# design.net
KiCad netlist of a schematic drawn in Altium Designer
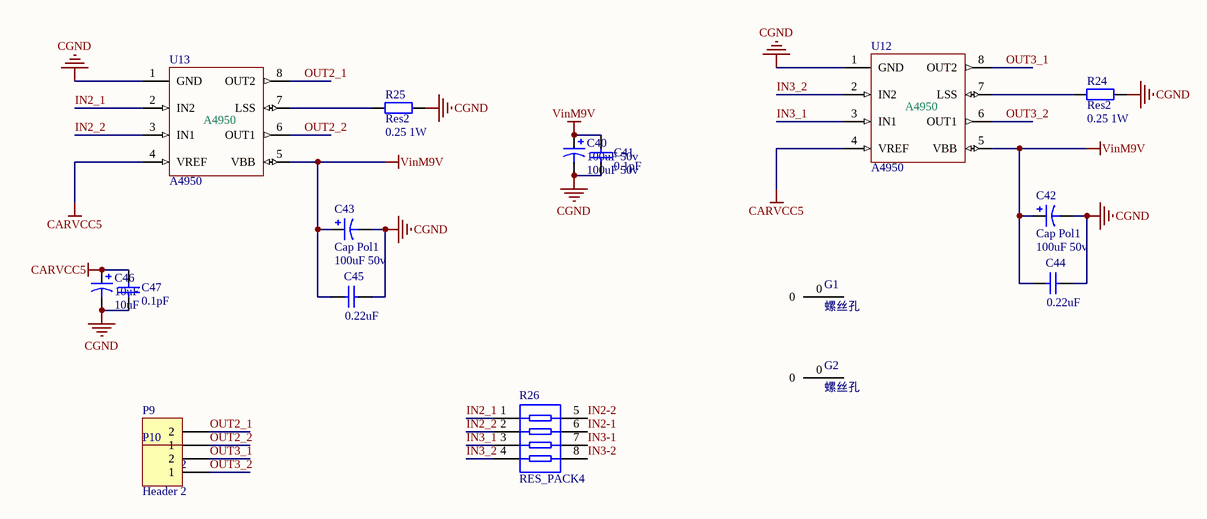
[diagram p0: 电机驱动.SchDoc]

(export (version "E")
  (design (tool "Eeschema 10.0.6"))
  (components
    (comp (ref "C40")
      (value "100uF 50v")
      (footprint "电容HONOR_63X77")
      (description "Polarized Capacitor (Radial)")
      (fields (field (name "ALTIUM_VALUE") "100uF 50v") (field (name "PUBLISHER") "Altium Limited"))
      (libsource (lib "Miscellaneous Devices") (part "Cap Pol1"))
    )
    (comp (ref "C41")
      (value "0.1pF")
      (footprint "LC-0603_C")
      (description "Capacitor")
      (fields (field (name "Comment") "Cap") (field (name "PUBLISHER") "Altium Limited"))
      (libsource (lib "Miscellaneous Devices") (part "Cap"))
    )
    (comp (ref "C42")
      (value "Cap Pol1")
      (footprint "100UF")
      (description "Polarized Capacitor (Radial)")
      (fields (field (name "ALTIUM_VALUE") "100uF 50v") (field (name "PUBLISHER") "Altium Limited"))
      (libsource (lib "Miscellaneous Devices") (part "Cap Pol1"))
    )
    (comp (ref "C43")
      (value "Cap Pol1")
      (footprint "100UF")
      (description "Polarized Capacitor (Radial)")
      (fields (field (name "ALTIUM_VALUE") "100uF 50v") (field (name "PUBLISHER") "Altium Limited"))
      (libsource (lib "Miscellaneous Devices") (part "Cap Pol1"))
    )
    (comp (ref "C44")
      (value "0.22uF")
      (footprint "LC-0603_C")
      (description "Capacitor")
      (fields (field (name "PUBLISHER") "Altium Limited"))
      (libsource (lib "Miscellaneous Devices") (part "Cap"))
    )
    (comp (ref "C45")
      (value "0.22uF")
      (footprint "LC-0603_C")
      (description "Capacitor")
      (fields (field (name "PUBLISHER") "Altium Limited"))
      (libsource (lib "Miscellaneous Devices") (part "Cap"))
    )
    (comp (ref "C46")
      (value "10uF")
      (footprint "电容HONOR_63X77")
      (description "Polarized Capacitor (Radial)")
      (fields (field (name "ALTIUM_VALUE") "10uF") (field (name "PUBLISHER") "Altium Limited"))
      (libsource (lib "Miscellaneous Devices") (part "Cap Pol1"))
    )
    (comp (ref "C47")
      (value "0.1pF")
      (footprint "LC-0603_C")
      (description "Capacitor")
      (fields (field (name "Comment") "Cap") (field (name "PUBLISHER") "Altium Limited"))
      (libsource (lib "Miscellaneous Devices") (part "Cap"))
    )
    (comp (ref "G1") (value "螺丝孔") (footprint "M3螺丝孔") (libsource (lib "ROS_CAR_LIB") (part "螺丝孔")))
    (comp (ref "G2") (value "螺丝孔") (footprint "M3螺丝孔") (libsource (lib "ROS_CAR_LIB") (part "螺丝孔")))
    (comp (ref "P9")
      (value "Header 2")
      (footprint "HDR1X2")
      (description "Header, 2-Pin")
      (fields (field (name "PUBLISHER") "Altium Limited"))
      (libsource (lib "Miscellaneous Connectors") (part "Header 2"))
    )
    (comp (ref "P10")
      (value "Header 2")
      (footprint "HDR1X2")
      (description "Header, 2-Pin")
      (fields (field (name "PUBLISHER") "Altium Limited"))
      (libsource (lib "Miscellaneous Connectors") (part "Header 2"))
    )
    (comp (ref "R24")
      (value "Res2")
      (footprint "LC-2512_R")
      (description "Resistor")
      (fields (field (name "ALTIUM_VALUE") "0.25 1W") (field (name "PUBLISHER") "Altium Limited"))
      (libsource (lib "Miscellaneous Devices") (part "Res2"))
    )
    (comp (ref "R25")
      (value "Res2")
      (footprint "LC-2512_R")
      (description "Resistor")
      (fields (field (name "ALTIUM_VALUE") "0.25 1W") (field (name "PUBLISHER") "Altium Limited"))
      (libsource (lib "Miscellaneous Devices") (part "Res2"))
    )
    (comp (ref "R26") (value "RES_PACK4") (footprint "RES4") (libsource (lib "ARAMYLIB") (part "RES_PACK4")))
    (comp (ref "U12")
      (value "A4950")
      (footprint "LC-SOIC-8_150mil")
      (libsource (lib "ROS_CAR_LIB") (part "A4950"))
    )
    (comp (ref "U13")
      (value "A4950")
      (footprint "LC-SOIC-8_150mil")
      (libsource (lib "ROS_CAR_LIB") (part "A4950"))
    )
  )
  (nets
    (net (code "1") (name "/IN2-1") (class "Default")
      (node (ref "R26") (pin "6") (pinfunction "6_6") (pintype "passive"))
    )
    (net (code "2") (name "/IN2-2") (class "Default")
      (node (ref "R26") (pin "5") (pinfunction "5_5") (pintype "passive"))
    )
    (net (code "3") (name "/IN2_1") (class "Default")
      (node (ref "R26") (pin "1") (pinfunction "1_1") (pintype "passive"))
      (node (ref "U13") (pin "2") (pinfunction "IN2_2") (pintype "input"))
    )
    (net (code "4") (name "/IN2_2") (class "Default")
      (node (ref "R26") (pin "2") (pinfunction "2_2") (pintype "passive"))
      (node (ref "U13") (pin "3") (pinfunction "IN1_3") (pintype "input"))
    )
    (net (code "5") (name "/IN3-1") (class "Default")
      (node (ref "R26") (pin "7") (pinfunction "7_7") (pintype "passive"))
    )
    (net (code "6") (name "/IN3-2") (class "Default")
      (node (ref "R26") (pin "8") (pinfunction "8_8") (pintype "passive"))
    )
    (net (code "7") (name "/IN3_1") (class "Default")
      (node (ref "R26") (pin "3") (pinfunction "3_3") (pintype "passive"))
      (node (ref "U12") (pin "3") (pinfunction "IN1_3") (pintype "input"))
    )
    (net (code "8") (name "/IN3_2") (class "Default")
      (node (ref "R26") (pin "4") (pinfunction "4_4") (pintype "passive"))
      (node (ref "U12") (pin "2") (pinfunction "IN2_2") (pintype "input"))
    )
    (net (code "9") (name "/OUT2_1") (class "Default")
      (node (ref "P9") (pin "2") (pinfunction "2_2") (pintype "passive"))
      (node (ref "U13") (pin "8") (pinfunction "OUT2_8") (pintype "output"))
    )
    (net (code "10") (name "/OUT2_2") (class "Default")
      (node (ref "P9") (pin "1") (pinfunction "1_1") (pintype "passive"))
      (node (ref "U13") (pin "6") (pinfunction "OUT1_6") (pintype "output"))
    )
    (net (code "11") (name "/OUT3_1") (class "Default")
      (node (ref "P10") (pin "2") (pinfunction "2_2") (pintype "passive"))
      (node (ref "U12") (pin "8") (pinfunction "OUT2_8") (pintype "output"))
    )
    (net (code "12") (name "/OUT3_2") (class "Default")
      (node (ref "P10") (pin "1") (pinfunction "1_1") (pintype "passive"))
      (node (ref "U12") (pin "6") (pinfunction "OUT1_6") (pintype "output"))
    )
    (net (code "13") (name "CARVCC5") (class "Default")
      (node (ref "C46") (pin "1") (pinfunction "1_1") (pintype "passive"))
      (node (ref "C47") (pin "1") (pinfunction "1_1") (pintype "passive"))
      (node (ref "U12") (pin "4") (pinfunction "VREF_4") (pintype "input"))
      (node (ref "U13") (pin "4") (pinfunction "VREF_4") (pintype "input"))
    )
    (net (code "14") (name "CGND") (class "Default")
      (node (ref "C40") (pin "2") (pinfunction "2_2") (pintype "passive"))
      (node (ref "C41") (pin "2") (pinfunction "2_2") (pintype "passive"))
      (node (ref "C42") (pin "2") (pinfunction "2_2") (pintype "passive"))
      (node (ref "C43") (pin "2") (pinfunction "2_2") (pintype "passive"))
      (node (ref "C44") (pin "2") (pinfunction "2_2") (pintype "passive"))
      (node (ref "C45") (pin "2") (pinfunction "2_2") (pintype "passive"))
      (node (ref "C46") (pin "2") (pinfunction "2_2") (pintype "passive"))
      (node (ref "C47") (pin "2") (pinfunction "2_2") (pintype "passive"))
      (node (ref "R24") (pin "2") (pinfunction "2_2") (pintype "passive"))
      (node (ref "R25") (pin "2") (pinfunction "2_2") (pintype "passive"))
      (node (ref "U12") (pin "1") (pinfunction "GND_1") (pintype "power_in"))
      (node (ref "U13") (pin "1") (pinfunction "GND_1") (pintype "power_in"))
    )
    (net (code "15") (name "Net-(U12-LSS)") (class "Default")
      (node (ref "R24") (pin "1") (pinfunction "1_1") (pintype "passive"))
      (node (ref "U12") (pin "7") (pinfunction "LSS_7") (pintype "bidirectional"))
    )
    (net (code "16") (name "Net-(U13-LSS)") (class "Default")
      (node (ref "R25") (pin "1") (pinfunction "1_1") (pintype "passive"))
      (node (ref "U13") (pin "7") (pinfunction "LSS_7") (pintype "bidirectional"))
    )
    (net (code "17") (name "VinM9V") (class "Default")
      (node (ref "C40") (pin "1") (pinfunction "1_1") (pintype "passive"))
      (node (ref "C41") (pin "1") (pinfunction "1_1") (pintype "passive"))
      (node (ref "C42") (pin "1") (pinfunction "1_1") (pintype "passive"))
      (node (ref "C43") (pin "1") (pinfunction "1_1") (pintype "passive"))
      (node (ref "C44") (pin "1") (pinfunction "1_1") (pintype "passive"))
      (node (ref "C45") (pin "1") (pinfunction "1_1") (pintype "passive"))
      (node (ref "U12") (pin "5") (pinfunction "VBB_5") (pintype "bidirectional"))
      (node (ref "U13") (pin "5") (pinfunction "VBB_5") (pintype "bidirectional"))
    )
    (net (code "18") (name "unconnected-(G1-Pad0)") (class "Default")
      (node (ref "G1") (pin "0") (pinfunction "0_0") (pintype "passive"))
    )
    (net (code "19") (name "unconnected-(G2-Pad0)") (class "Default")
      (node (ref "G2") (pin "0") (pinfunction "0_0") (pintype "passive"))
    )
  )
)
